# alexawrover.net
KiCad netlist of a schematic drawn in EAGLE
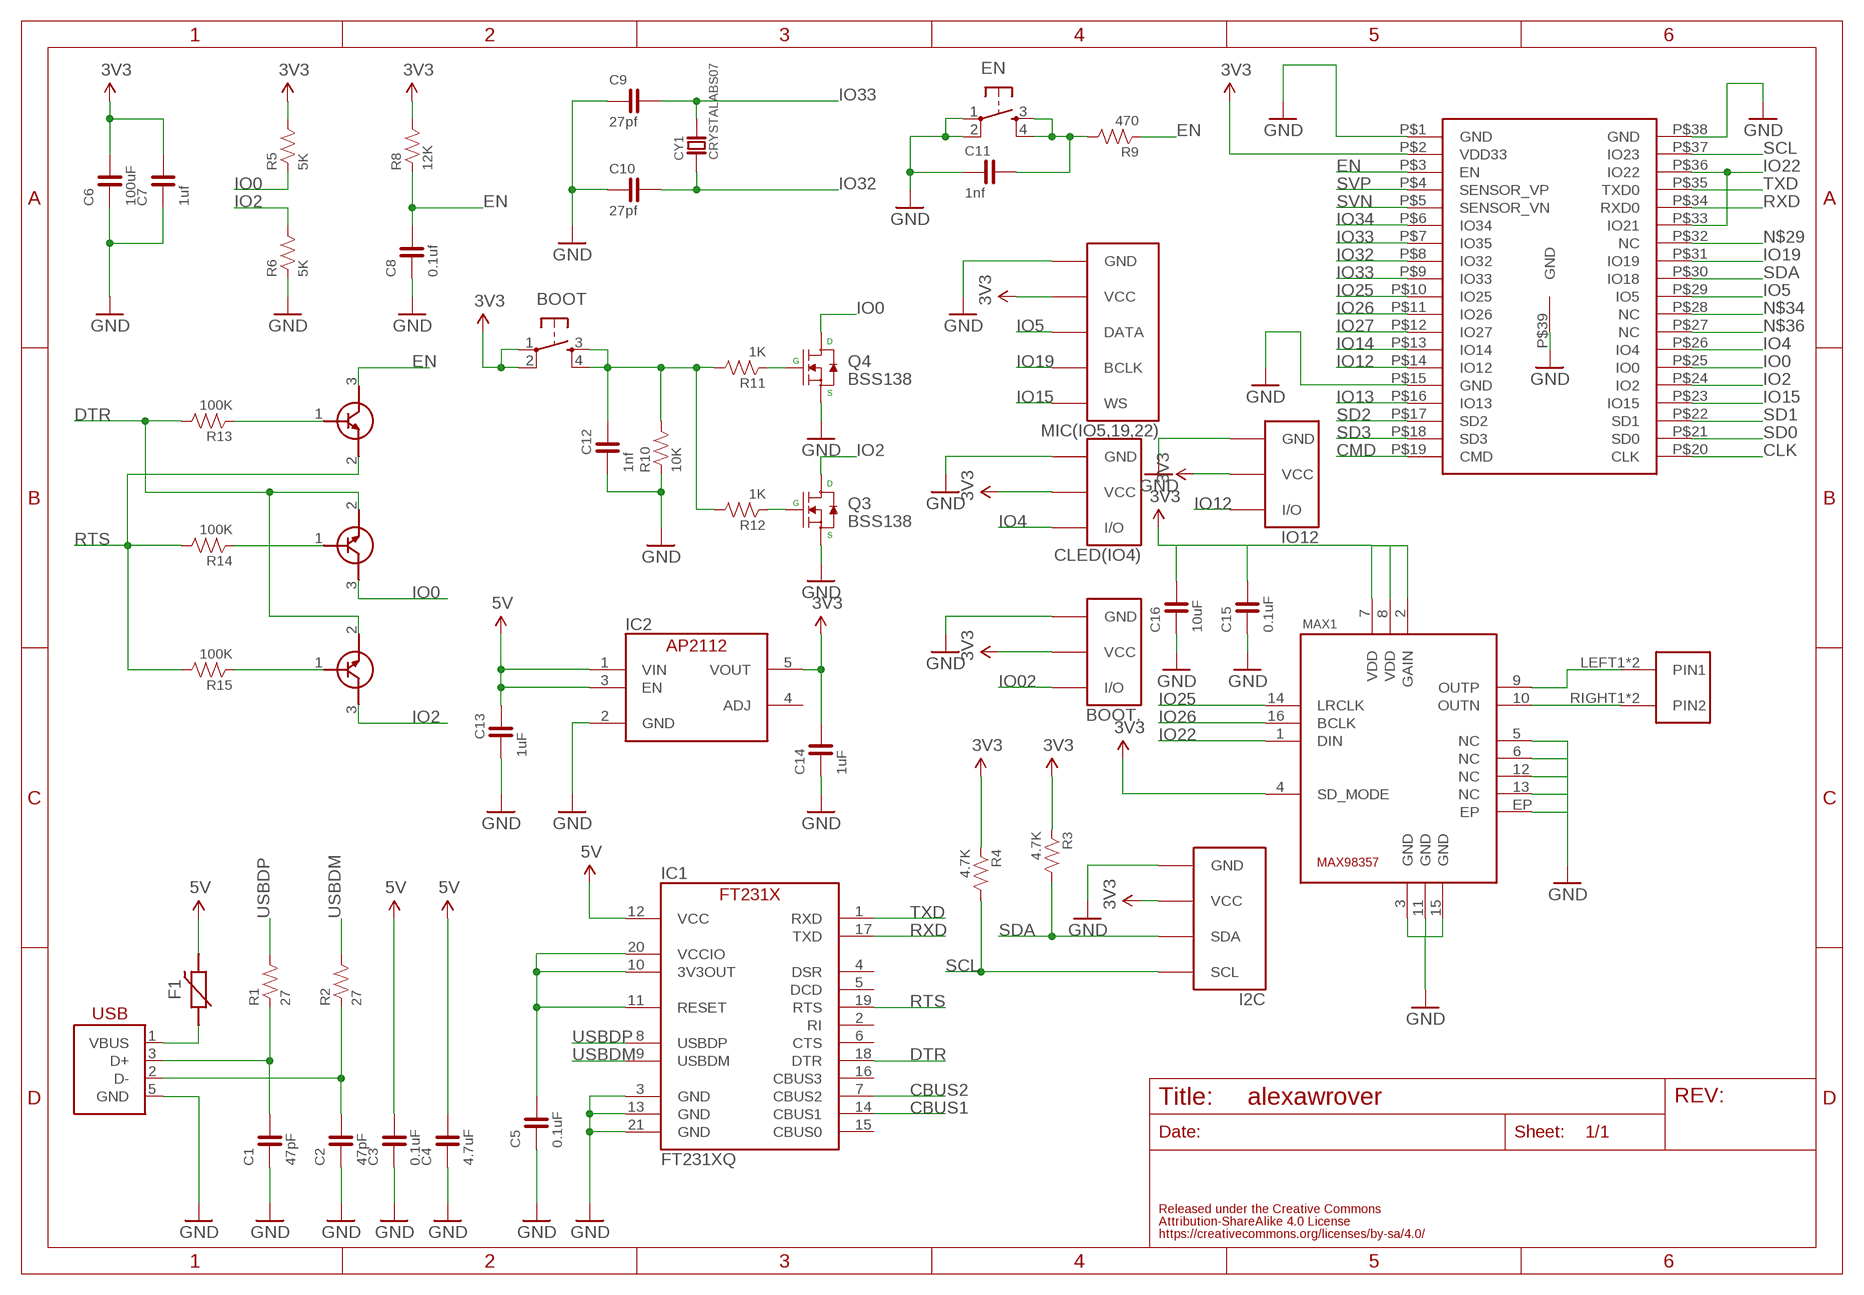
[diagram p0: schematic, sheet 1]

(export (version "E")
  (design (tool "Eeschema 10.0.6"))
  (components
    (comp (ref "BOOT")
      (value "TACT-SWITCH-SMD_KMR2")
      (footprint "eagle-import:KMR2")
      (libsource (lib "eagle-import") (part "TACT-SWITCH-SMD_KMR2"))
    )
    (comp (ref "BOOT.")
      (value "BUTTON")
      (footprint "eagle-import:FABO_BRICK_3PIN_B03B-PASK-1_NAME_BOTTOM")
      (libsource (lib "eagle-import") (part "FABO_BRICK_3PIN-03B-PASK-1_NAME_BOTTOM"))
    )
    (comp (ref "C1")
      (value "47pF")
      (footprint "eagle-import:0603-NARROW")
      (libsource (lib "eagle-import") (part "CAPACITOR-0603_NARROW"))
    )
    (comp (ref "C2")
      (value "47pF")
      (footprint "eagle-import:0603-NARROW")
      (libsource (lib "eagle-import") (part "CAPACITOR-0603_NARROW"))
    )
    (comp (ref "C3")
      (value "0.1uF")
      (footprint "eagle-import:0603-NARROW")
      (libsource (lib "eagle-import") (part "CAPACITOR-0603_NARROW"))
    )
    (comp (ref "C4")
      (value "4.7uF")
      (footprint "eagle-import:0603-NARROW")
      (libsource (lib "eagle-import") (part "CAPACITOR-0603_NARROW"))
    )
    (comp (ref "C5")
      (value "0.1uF")
      (footprint "eagle-import:0603-NARROW")
      (libsource (lib "eagle-import") (part "CAPACITOR-0603_NARROW"))
    )
    (comp (ref "C6")
      (value "100uF")
      (footprint "eagle-import:1206")
      (libsource (lib "eagle-import") (part "CAPACITOR-1206"))
    )
    (comp (ref "C7")
      (value "1uf")
      (footprint "eagle-import:0603-NARROW")
      (libsource (lib "eagle-import") (part "CAPACITOR-0603_NARROW"))
    )
    (comp (ref "C8")
      (value "0.1uf")
      (footprint "eagle-import:0603-NARROW")
      (libsource (lib "eagle-import") (part "CAPACITOR-0603_NARROW"))
    )
    (comp (ref "C9")
      (value "27pf")
      (footprint "eagle-import:0603-NARROW")
      (libsource (lib "eagle-import") (part "CAPACITOR-0603_NARROW"))
    )
    (comp (ref "C10")
      (value "27pf")
      (footprint "eagle-import:0603-NARROW")
      (libsource (lib "eagle-import") (part "CAPACITOR-0603_NARROW"))
    )
    (comp (ref "C11")
      (value "1nf")
      (footprint "eagle-import:0603-NARROW")
      (libsource (lib "eagle-import") (part "CAPACITOR-0603_NARROW"))
    )
    (comp (ref "C12")
      (value "1nf")
      (footprint "eagle-import:0603-NARROW")
      (libsource (lib "eagle-import") (part "CAPACITOR-0603_NARROW"))
    )
    (comp (ref "C13")
      (value "1uF")
      (footprint "eagle-import:0603")
      (libsource (lib "eagle-import") (part "CAPACITOR-0603"))
    )
    (comp (ref "C14")
      (value "1uF")
      (footprint "eagle-import:0603")
      (libsource (lib "eagle-import") (part "CAPACITOR-0603"))
    )
    (comp (ref "C15")
      (value "0.1uF")
      (footprint "eagle-import:0603")
      (libsource (lib "eagle-import") (part "CAPACITOR-0603"))
    )
    (comp (ref "C16")
      (value "10uF")
      (footprint "eagle-import:0603")
      (libsource (lib "eagle-import") (part "CAPACITOR-0603"))
    )
    (comp (ref "CLED(IO4)")
      (value "FABO_BRICK_3PIN-03B-PASK-1_NAME_BOTTOM")
      (footprint "eagle-import:FABO_BRICK_3PIN_B03B-PASK-1_NAME_BOTTOM")
      (libsource (lib "eagle-import") (part "FABO_BRICK_3PIN-03B-PASK-1_NAME_BOTTOM"))
    )
    (comp (ref "CY1")
      (value "CRYSTALABS07")
      (footprint "eagle-import:ABRACOM-ABS07-32.768KHZ")
      (libsource (lib "eagle-import") (part "CRYSTALABS07"))
    )
    (comp (ref "EN")
      (value "TACT-SWITCH-SMD_KMR2")
      (footprint "eagle-import:KMR2")
      (libsource (lib "eagle-import") (part "TACT-SWITCH-SMD_KMR2"))
    )
    (comp (ref "F1")
      (value "POLYSWITCH")
      (footprint "eagle-import:NANOSMDC035F")
      (libsource (lib "eagle-import") (part "POLYSWITCH"))
    )
    (comp (ref "I2C")
      (value "FABO_BRICK_I2C-B04B-PASK-1")
      (footprint "eagle-import:FABO_BRICK_I2C_B04B-PASK-1")
      (libsource (lib "eagle-import") (part "FABO_BRICK_I2C-B04B-PASK-1"))
    )
    (comp (ref "IC1")
      (value "FT231XQ")
      (footprint "eagle-import:QFN-20_FT231X")
      (libsource (lib "eagle-import") (part "FT231XQ"))
    )
    (comp (ref "IC2")
      (value "AP2112K-3.3TRG1")
      (footprint "eagle-import:SOT-23-5")
      (libsource (lib "eagle-import") (part "AP2112K-3.3TRG1"))
    )
    (comp (ref "IO12")
      (value "FABO_BRICK_3PIN-03B-PASK-1_NAME_BOTTOM")
      (footprint "eagle-import:FABO_BRICK_3PIN_B03B-PASK-1_NAME_BOTTOM")
      (libsource (lib "eagle-import") (part "FABO_BRICK_3PIN-03B-PASK-1_NAME_BOTTOM"))
    )
    (comp (ref "MAX1")
      (value "MA-MAX98357")
      (footprint "eagle-import:MAXIM-MAX98357")
      (libsource (lib "eagle-import") (part "MA-MAX98357"))
    )
    (comp (ref "MIC(IO5,19,22)")
      (value "FABO_BRICK_I2STOP")
      (footprint "eagle-import:FABO_BRICK_I2S_B05B-PARK-1")
      (libsource (lib "eagle-import") (part "FABO_BRICK_I2STOP"))
    )
    (comp (ref "Q3")
      (value "BSS138")
      (footprint "eagle-import:SOT23-3")
      (libsource (lib "eagle-import") (part "MOSFET-N-BSS138"))
    )
    (comp (ref "Q4")
      (value "BSS138")
      (footprint "eagle-import:SOT23-3")
      (libsource (lib "eagle-import") (part "MOSFET-N-BSS138"))
    )
    (comp (ref "R1")
      (value "27")
      (footprint "eagle-import:0603-NARROW")
      (libsource (lib "eagle-import") (part "RESISTOR-0603-NARROW"))
    )
    (comp (ref "R2")
      (value "27")
      (footprint "eagle-import:0603-NARROW")
      (libsource (lib "eagle-import") (part "RESISTOR-0603-NARROW"))
    )
    (comp (ref "R3")
      (value "4.7K")
      (footprint "eagle-import:0603-NARROW")
      (libsource (lib "eagle-import") (part "RESISTOR-0603-NARROW"))
    )
    (comp (ref "R4")
      (value "4.7K")
      (footprint "eagle-import:0603-NARROW")
      (libsource (lib "eagle-import") (part "RESISTOR-0603-NARROW"))
    )
    (comp (ref "R5")
      (value "5K")
      (footprint "eagle-import:0603-NARROW")
      (libsource (lib "eagle-import") (part "RESISTOR-0603-NARROW"))
    )
    (comp (ref "R6")
      (value "5K")
      (footprint "eagle-import:0603-NARROW")
      (libsource (lib "eagle-import") (part "RESISTOR-0603-NARROW"))
    )
    (comp (ref "R8")
      (value "12K")
      (footprint "eagle-import:0603-NARROW")
      (libsource (lib "eagle-import") (part "RESISTOR-0603-NARROW"))
    )
    (comp (ref "R9")
      (value "470")
      (footprint "eagle-import:0603-NARROW")
      (libsource (lib "eagle-import") (part "RESISTOR-0603-NARROW"))
    )
    (comp (ref "R10")
      (value "10K")
      (footprint "eagle-import:0603-NARROW")
      (libsource (lib "eagle-import") (part "RESISTOR-0603-NARROW"))
    )
    (comp (ref "R11")
      (value "1K")
      (footprint "eagle-import:0603-NARROW")
      (libsource (lib "eagle-import") (part "RESISTOR-0603-NARROW"))
    )
    (comp (ref "R12")
      (value "1K")
      (footprint "eagle-import:0603-NARROW")
      (libsource (lib "eagle-import") (part "RESISTOR-0603-NARROW"))
    )
    (comp (ref "R13")
      (value "100K")
      (footprint "eagle-import:0603-NARROW")
      (libsource (lib "eagle-import") (part "RESISTOR-0603-NARROW"))
    )
    (comp (ref "R14")
      (value "100K")
      (footprint "eagle-import:0603-NARROW")
      (libsource (lib "eagle-import") (part "RESISTOR-0603-NARROW"))
    )
    (comp (ref "R15")
      (value "100K")
      (footprint "eagle-import:0603-NARROW")
      (libsource (lib "eagle-import") (part "RESISTOR-0603-NARROW"))
    )
    (comp (ref "T1")
      (value "TRANSISTORMMBT2222")
      (footprint "eagle-import:SOT-23")
      (libsource (lib "eagle-import") (part "TRANSISTORMMBT2222"))
    )
    (comp (ref "T2")
      (value "TRANSISTORMMBT2222")
      (footprint "eagle-import:SOT-23")
      (libsource (lib "eagle-import") (part "TRANSISTORMMBT2222"))
    )
    (comp (ref "T3")
      (value "TRANSISTORMMBT2222")
      (footprint "eagle-import:SOT-23")
      (libsource (lib "eagle-import") (part "TRANSISTORMMBT2222"))
    )
    (comp (ref "U$1")
      (value "ESP32-WROVER")
      (footprint "eagle-import:ESP32-WROVER")
      (libsource (lib "eagle-import") (part "ESP32-WROVER"))
    )
    (comp (ref "U$4")
      (value "ML-1400-S1")
      (footprint "eagle-import:ML-1400-S1")
      (libsource (lib "eagle-import") (part "ML-1400-S1"))
    )
    (comp (ref "USB1")
      (value "USB-MICRO_B_SMT_HIROSE")
      (footprint "eagle-import:ZX62R-B-5P")
      (libsource (lib "eagle-import") (part "USB-MICRO_B_SMT_HIROSE"))
    )
  )
  (nets
    (net (code "1") (name "/CBUS1") (class "Default")
      (node (ref "IC1") (pin "14") (pinfunction "CBUS1_14") (pintype "bidirectional"))
    )
    (net (code "2") (name "/CBUS2") (class "Default")
      (node (ref "IC1") (pin "7") (pinfunction "CBUS2_7") (pintype "bidirectional"))
    )
    (net (code "3") (name "/CLK") (class "Default")
      (node (ref "U$1") (pin "P$20") (pinfunction "CLK_P$20") (pintype "bidirectional"))
    )
    (net (code "4") (name "/CMD") (class "Default")
      (node (ref "U$1") (pin "P$19") (pinfunction "CMD_P$19") (pintype "bidirectional"))
    )
    (net (code "5") (name "/DTR") (class "Default")
      (node (ref "IC1") (pin "18") (pinfunction "DTR_18") (pintype "bidirectional"))
      (node (ref "R13") (pin "2") (pinfunction "2_2") (pintype "bidirectional"))
      (node (ref "T2") (pin "2") (pinfunction "E_2") (pintype "bidirectional"))
      (node (ref "T3") (pin "2") (pinfunction "E_2") (pintype "bidirectional"))
    )
    (net (code "6") (name "/EN") (class "Default")
      (node (ref "C8") (pin "2") (pinfunction "2_2") (pintype "passive"))
      (node (ref "R8") (pin "1") (pinfunction "1_1") (pintype "bidirectional"))
      (node (ref "R9") (pin "1") (pinfunction "1_1") (pintype "bidirectional"))
      (node (ref "T1") (pin "3") (pinfunction "C_3") (pintype "bidirectional"))
      (node (ref "U$1") (pin "P$3") (pinfunction "EN_P$3") (pintype "bidirectional"))
    )
    (net (code "7") (name "/IO0") (class "Default")
      (node (ref "Q4") (pin "3") (pinfunction "D_3") (pintype "passive"))
      (node (ref "R5") (pin "1") (pinfunction "1_1") (pintype "bidirectional"))
      (node (ref "T2") (pin "3") (pinfunction "C_3") (pintype "bidirectional"))
      (node (ref "U$1") (pin "P$25") (pinfunction "IO0_P$25") (pintype "bidirectional"))
    )
    (net (code "8") (name "/IO2") (class "Default")
      (node (ref "Q3") (pin "3") (pinfunction "D_3") (pintype "passive"))
      (node (ref "R6") (pin "2") (pinfunction "2_2") (pintype "bidirectional"))
      (node (ref "T3") (pin "3") (pinfunction "C_3") (pintype "bidirectional"))
      (node (ref "U$1") (pin "P$24") (pinfunction "IO2_P$24") (pintype "bidirectional"))
    )
    (net (code "9") (name "/IO02") (class "Default")
      (node (ref "BOOT.") (pin "I/O") (pinfunction "I/O_I/O") (pintype "bidirectional"))
    )
    (net (code "10") (name "/IO4") (class "Default")
      (node (ref "CLED(IO4)") (pin "I/O") (pinfunction "I/O_I/O") (pintype "bidirectional"))
      (node (ref "U$1") (pin "P$26") (pinfunction "IO4_P$26") (pintype "bidirectional"))
    )
    (net (code "11") (name "/IO5") (class "Default")
      (node (ref "MIC(IO5,19,22)") (pin "DATA") (pinfunction "DATA_DATA") (pintype "bidirectional"))
      (node (ref "U$1") (pin "P$29") (pinfunction "IO5_P$29") (pintype "bidirectional"))
    )
    (net (code "12") (name "/IO12") (class "Default")
      (node (ref "IO12") (pin "I/O") (pinfunction "I/O_I/O") (pintype "bidirectional"))
      (node (ref "U$1") (pin "P$14") (pinfunction "IO12_P$14") (pintype "bidirectional"))
    )
    (net (code "13") (name "/IO13") (class "Default")
      (node (ref "U$1") (pin "P$16") (pinfunction "IO13_P$16") (pintype "bidirectional"))
    )
    (net (code "14") (name "/IO14") (class "Default")
      (node (ref "U$1") (pin "P$13") (pinfunction "IO14_P$13") (pintype "bidirectional"))
    )
    (net (code "15") (name "/IO15") (class "Default")
      (node (ref "MIC(IO5,19,22)") (pin "WS") (pinfunction "WS_WS") (pintype "bidirectional"))
      (node (ref "U$1") (pin "P$23") (pinfunction "IO15_P$23") (pintype "bidirectional"))
    )
    (net (code "16") (name "/IO19") (class "Default")
      (node (ref "MIC(IO5,19,22)") (pin "BCLK") (pinfunction "BCLK_BCLK") (pintype "bidirectional"))
      (node (ref "U$1") (pin "P$31") (pinfunction "IO19_P$31") (pintype "bidirectional"))
    )
    (net (code "17") (name "/IO22") (class "Default")
      (node (ref "MAX1") (pin "1") (pinfunction "DIN_1") (pintype "bidirectional"))
      (node (ref "U$1") (pin "P$33") (pinfunction "IO21_P$33") (pintype "bidirectional"))
      (node (ref "U$1") (pin "P$36") (pinfunction "IO22_P$36") (pintype "bidirectional"))
    )
    (net (code "18") (name "/IO25") (class "Default")
      (node (ref "MAX1") (pin "14") (pinfunction "LRCLK_14") (pintype "bidirectional"))
      (node (ref "U$1") (pin "P$10") (pinfunction "IO25_P$10") (pintype "bidirectional"))
    )
    (net (code "19") (name "/IO26") (class "Default")
      (node (ref "MAX1") (pin "16") (pinfunction "BCLK_16") (pintype "bidirectional"))
      (node (ref "U$1") (pin "P$11") (pinfunction "IO26_P$11") (pintype "bidirectional"))
    )
    (net (code "20") (name "/IO27") (class "Default")
      (node (ref "U$1") (pin "P$12") (pinfunction "IO27_P$12") (pintype "bidirectional"))
    )
    (net (code "21") (name "/IO32") (class "Default")
      (node (ref "C10") (pin "2") (pinfunction "2_2") (pintype "passive"))
      (node (ref "CY1") (pin "P$1") (pinfunction "P$1_P$1") (pintype "bidirectional"))
      (node (ref "U$1") (pin "P$8") (pinfunction "IO32_P$8") (pintype "bidirectional"))
    )
    (net (code "22") (name "/IO33") (class "Default")
      (node (ref "C9") (pin "2") (pinfunction "2_2") (pintype "passive"))
      (node (ref "CY1") (pin "P$2") (pinfunction "P$2_P$2") (pintype "bidirectional"))
      (node (ref "U$1") (pin "P$7") (pinfunction "IO35_P$7") (pintype "bidirectional"))
      (node (ref "U$1") (pin "P$9") (pinfunction "IO33_P$9") (pintype "bidirectional"))
    )
    (net (code "23") (name "/IO34") (class "Default")
      (node (ref "U$1") (pin "P$6") (pinfunction "IO34_P$6") (pintype "bidirectional"))
    )
    (net (code "24") (name "/N$29") (class "Default")
      (node (ref "U$1") (pin "P$32") (pinfunction "NC_P$32") (pintype "bidirectional"))
    )
    (net (code "25") (name "/N$34") (class "Default")
      (node (ref "U$1") (pin "P$28") (pinfunction "NC_P$28") (pintype "bidirectional"))
    )
    (net (code "26") (name "/N$36") (class "Default")
      (node (ref "U$1") (pin "P$27") (pinfunction "NC_P$27") (pintype "bidirectional"))
    )
    (net (code "27") (name "/RTS") (class "Default")
      (node (ref "IC1") (pin "19") (pinfunction "RTS_19") (pintype "bidirectional"))
      (node (ref "R14") (pin "2") (pinfunction "2_2") (pintype "bidirectional"))
      (node (ref "R15") (pin "2") (pinfunction "2_2") (pintype "bidirectional"))
      (node (ref "T1") (pin "2") (pinfunction "E_2") (pintype "bidirectional"))
    )
    (net (code "28") (name "/RXD") (class "Default")
      (node (ref "IC1") (pin "17") (pinfunction "TXD_17") (pintype "bidirectional"))
      (node (ref "U$1") (pin "P$34") (pinfunction "RXD0_P$34") (pintype "bidirectional"))
    )
    (net (code "29") (name "/SCL") (class "Default")
      (node (ref "I2C") (pin "SCL") (pinfunction "SCL_SCL") (pintype "bidirectional"))
      (node (ref "R4") (pin "2") (pinfunction "2_2") (pintype "bidirectional"))
      (node (ref "U$1") (pin "P$37") (pinfunction "IO23_P$37") (pintype "bidirectional"))
    )
    (net (code "30") (name "/SD0") (class "Default")
      (node (ref "U$1") (pin "P$21") (pinfunction "SD0_P$21") (pintype "bidirectional"))
    )
    (net (code "31") (name "/SD1") (class "Default")
      (node (ref "U$1") (pin "P$22") (pinfunction "SD1_P$22") (pintype "bidirectional"))
    )
    (net (code "32") (name "/SD2") (class "Default")
      (node (ref "U$1") (pin "P$17") (pinfunction "SD2_P$17") (pintype "bidirectional"))
    )
    (net (code "33") (name "/SD3") (class "Default")
      (node (ref "U$1") (pin "P$18") (pinfunction "SD3_P$18") (pintype "bidirectional"))
    )
    (net (code "34") (name "/SDA") (class "Default")
      (node (ref "I2C") (pin "SDA") (pinfunction "SDA_SDA") (pintype "bidirectional"))
      (node (ref "R3") (pin "2") (pinfunction "2_2") (pintype "bidirectional"))
      (node (ref "U$1") (pin "P$30") (pinfunction "IO18_P$30") (pintype "bidirectional"))
    )
    (net (code "35") (name "/SVN") (class "Default")
      (node (ref "U$1") (pin "P$5") (pinfunction "SENSOR_VN_P$5") (pintype "bidirectional"))
    )
    (net (code "36") (name "/SVP") (class "Default")
      (node (ref "U$1") (pin "P$4") (pinfunction "SENSOR_VP_P$4") (pintype "bidirectional"))
    )
    (net (code "37") (name "/TXD") (class "Default")
      (node (ref "IC1") (pin "1") (pinfunction "RXD_1") (pintype "bidirectional"))
      (node (ref "U$1") (pin "P$35") (pinfunction "TXD0_P$35") (pintype "bidirectional"))
    )
    (net (code "38") (name "/USBDM") (class "Default")
      (node (ref "IC1") (pin "9") (pinfunction "USBDM_9") (pintype "bidirectional"))
      (node (ref "R2") (pin "2") (pinfunction "2_2") (pintype "bidirectional"))
    )
    (net (code "39") (name "/USBDP") (class "Default")
      (node (ref "IC1") (pin "8") (pinfunction "USBDP_8") (pintype "bidirectional"))
      (node (ref "R1") (pin "2") (pinfunction "2_2") (pintype "bidirectional"))
    )
    (net (code "40") (name "3V3") (class "Default")
      (node (ref "BOOT") (pin "1") (pinfunction "1_1") (pintype "passive"))
      (node (ref "BOOT") (pin "2") (pinfunction "2_2") (pintype "passive"))
      (node (ref "BOOT.") (pin "VCC") (pinfunction "VCC_VCC") (pintype "bidirectional"))
      (node (ref "C14") (pin "2") (pinfunction "2_2") (pintype "passive"))
      (node (ref "C15") (pin "2") (pinfunction "2_2") (pintype "passive"))
      (node (ref "C16") (pin "2") (pinfunction "2_2") (pintype "passive"))
      (node (ref "C6") (pin "-") (pinfunction "2_-") (pintype "passive"))
      (node (ref "C7") (pin "2") (pinfunction "2_2") (pintype "passive"))
      (node (ref "CLED(IO4)") (pin "VCC") (pinfunction "VCC_VCC") (pintype "bidirectional"))
      (node (ref "I2C") (pin "VCC") (pinfunction "VCC_VCC") (pintype "bidirectional"))
      (node (ref "IC2") (pin "5") (pinfunction "VOUT_5") (pintype "bidirectional"))
      (node (ref "IO12") (pin "VCC") (pinfunction "VCC_VCC") (pintype "bidirectional"))
      (node (ref "MAX1") (pin "2") (pinfunction "GAIN_2") (pintype "bidirectional"))
      (node (ref "MAX1") (pin "4") (pinfunction "SD_MODE_4") (pintype "bidirectional"))
      (node (ref "MAX1") (pin "7") (pinfunction "VDD_7") (pintype "bidirectional"))
      (node (ref "MAX1") (pin "8") (pinfunction "VDD_8") (pintype "bidirectional"))
      (node (ref "MIC(IO5,19,22)") (pin "VCC") (pinfunction "VCC_VCC") (pintype "bidirectional"))
      (node (ref "R3") (pin "1") (pinfunction "1_1") (pintype "bidirectional"))
      (node (ref "R4") (pin "1") (pinfunction "1_1") (pintype "bidirectional"))
      (node (ref "R5") (pin "2") (pinfunction "2_2") (pintype "bidirectional"))
      (node (ref "R8") (pin "2") (pinfunction "2_2") (pintype "bidirectional"))
      (node (ref "U$1") (pin "P$2") (pinfunction "VDD33_P$2") (pintype "bidirectional"))
    )
    (net (code "41") (name "5V") (class "Default")
      (node (ref "C13") (pin "2") (pinfunction "2_2") (pintype "passive"))
      (node (ref "C3") (pin "2") (pinfunction "2_2") (pintype "passive"))
      (node (ref "C4") (pin "2") (pinfunction "2_2") (pintype "passive"))
      (node (ref "F1") (pin "2") (pinfunction "2_2") (pintype "bidirectional"))
      (node (ref "IC1") (pin "12") (pinfunction "VCC_12") (pintype "bidirectional"))
      (node (ref "IC2") (pin "1") (pinfunction "VIN_1") (pintype "bidirectional"))
      (node (ref "IC2") (pin "3") (pinfunction "EN_3") (pintype "bidirectional"))
    )
    (net (code "42") (name "GND") (class "Default")
      (node (ref "BOOT.") (pin "GND") (pinfunction "GND_GND") (pintype "bidirectional"))
      (node (ref "C1") (pin "1") (pinfunction "1_1") (pintype "passive"))
      (node (ref "C10") (pin "1") (pinfunction "1_1") (pintype "passive"))
      (node (ref "C11") (pin "1") (pinfunction "1_1") (pintype "passive"))
      (node (ref "C12") (pin "1") (pinfunction "1_1") (pintype "passive"))
      (node (ref "C13") (pin "1") (pinfunction "1_1") (pintype "passive"))
      (node (ref "C14") (pin "1") (pinfunction "1_1") (pintype "passive"))
      (node (ref "C15") (pin "1") (pinfunction "1_1") (pintype "passive"))
      (node (ref "C16") (pin "1") (pinfunction "1_1") (pintype "passive"))
      (node (ref "C2") (pin "1") (pinfunction "1_1") (pintype "passive"))
      (node (ref "C3") (pin "1") (pinfunction "1_1") (pintype "passive"))
      (node (ref "C4") (pin "1") (pinfunction "1_1") (pintype "passive"))
      (node (ref "C5") (pin "1") (pinfunction "1_1") (pintype "passive"))
      (node (ref "C6") (pin "+") (pinfunction "1_+") (pintype "passive"))
      (node (ref "C7") (pin "1") (pinfunction "1_1") (pintype "passive"))
      (node (ref "C8") (pin "1") (pinfunction "1_1") (pintype "passive"))
      (node (ref "C9") (pin "1") (pinfunction "1_1") (pintype "passive"))
      (node (ref "CLED(IO4)") (pin "GND") (pinfunction "GND_GND") (pintype "bidirectional"))
      (node (ref "EN") (pin "1") (pinfunction "1_1") (pintype "passive"))
      (node (ref "EN") (pin "2") (pinfunction "2_2") (pintype "passive"))
      (node (ref "I2C") (pin "GND") (pinfunction "GND_GND") (pintype "bidirectional"))
      (node (ref "IC1") (pin "13") (pinfunction "GND_13") (pintype "bidirectional"))
      (node (ref "IC1") (pin "21") (pinfunction "GND_21") (pintype "bidirectional"))
      (node (ref "IC1") (pin "3") (pinfunction "GND_3") (pintype "bidirectional"))
      (node (ref "IC2") (pin "2") (pinfunction "GND_2") (pintype "bidirectional"))
      (node (ref "IO12") (pin "GND") (pinfunction "GND_GND") (pintype "bidirectional"))
      (node (ref "MAX1") (pin "11") (pinfunction "GND_11") (pintype "bidirectional"))
      (node (ref "MAX1") (pin "12") (pinfunction "NC_12") (pintype "bidirectional"))
      (node (ref "MAX1") (pin "13") (pinfunction "NC_13") (pintype "bidirectional"))
      (node (ref "MAX1") (pin "15") (pinfunction "GND_15") (pintype "bidirectional"))
      (node (ref "MAX1") (pin "3") (pinfunction "GND_3") (pintype "bidirectional"))
      (node (ref "MAX1") (pin "5") (pinfunction "NC_5") (pintype "bidirectional"))
      (node (ref "MAX1") (pin "6") (pinfunction "NC_6") (pintype "bidirectional"))
      (node (ref "MAX1") (pin "EP") (pinfunction "EP_EP") (pintype "bidirectional"))
      (node (ref "MIC(IO5,19,22)") (pin "GND") (pinfunction "GND_GND") (pintype "bidirectional"))
      (node (ref "Q3") (pin "2") (pinfunction "S_2") (pintype "passive"))
      (node (ref "Q4") (pin "2") (pinfunction "S_2") (pintype "passive"))
      (node (ref "R10") (pin "1") (pinfunction "1_1") (pintype "bidirectional"))
      (node (ref "R6") (pin "1") (pinfunction "1_1") (pintype "bidirectional"))
      (node (ref "U$1") (pin "P$1") (pinfunction "GND_P$1") (pintype "bidirectional"))
      (node (ref "U$1") (pin "P$15") (pinfunction "GND_P$15") (pintype "bidirectional"))
      (node (ref "U$1") (pin "P$38") (pinfunction "GND_P$38") (pintype "bidirectional"))
      (node (ref "U$1") (pin "P$39") (pinfunction "GND_P$39") (pintype "bidirectional"))
      (node (ref "USB1") (pin "5") (pinfunction "GND_5") (pintype "bidirectional"))
    )
    (net (code "43") (name "Net-(BOOT-Pad3)") (class "Default")
      (node (ref "BOOT") (pin "3") (pinfunction "3_3") (pintype "passive"))
      (node (ref "BOOT") (pin "4") (pinfunction "4_4") (pintype "passive"))
      (node (ref "C12") (pin "2") (pinfunction "2_2") (pintype "passive"))
      (node (ref "R10") (pin "2") (pinfunction "2_2") (pintype "bidirectional"))
      (node (ref "R11") (pin "2") (pinfunction "2_2") (pintype "bidirectional"))
      (node (ref "R12") (pin "2") (pinfunction "2_2") (pintype "bidirectional"))
    )
    (net (code "44") (name "Net-(C11-Pad2)") (class "Default")
      (node (ref "C11") (pin "2") (pinfunction "2_2") (pintype "passive"))
      (node (ref "EN") (pin "3") (pinfunction "3_3") (pintype "passive"))
      (node (ref "EN") (pin "4") (pinfunction "4_4") (pintype "passive"))
      (node (ref "R9") (pin "2") (pinfunction "2_2") (pintype "bidirectional"))
    )
    (net (code "45") (name "Net-(IC1-3V3OUT)") (class "Default")
      (node (ref "C5") (pin "2") (pinfunction "2_2") (pintype "passive"))
      (node (ref "IC1") (pin "10") (pinfunction "3V3OUT_10") (pintype "bidirectional"))
      (node (ref "IC1") (pin "11") (pinfunction "RESET_11") (pintype "bidirectional"))
      (node (ref "IC1") (pin "20") (pinfunction "VCCIO_20") (pintype "bidirectional"))
    )
    (net (code "46") (name "Net-(MAX1-OUTN)") (class "Default")
      (node (ref "MAX1") (pin "10") (pinfunction "OUTN_10") (pintype "bidirectional"))
      (node (ref "U$4") (pin "RIGHT1") (pinfunction "PIN2_RIGHT1") (pintype "bidirectional"))
      (node (ref "U$4") (pin "RIGHT2") (pinfunction "PIN2_RIGHT2") (pintype "bidirectional"))
    )
    (net (code "47") (name "Net-(MAX1-OUTP)") (class "Default")
      (node (ref "MAX1") (pin "9") (pinfunction "OUTP_9") (pintype "bidirectional"))
      (node (ref "U$4") (pin "LEFT1") (pinfunction "PIN1_LEFT1") (pintype "bidirectional"))
      (node (ref "U$4") (pin "LEFT2") (pinfunction "PIN1_LEFT2") (pintype "bidirectional"))
    )
    (net (code "48") (name "Net-(Q3-G)") (class "Default")
      (node (ref "Q3") (pin "1") (pinfunction "G_1") (pintype "passive"))
      (node (ref "R12") (pin "1") (pinfunction "1_1") (pintype "bidirectional"))
    )
    (net (code "49") (name "Net-(Q4-G)") (class "Default")
      (node (ref "Q4") (pin "1") (pinfunction "G_1") (pintype "passive"))
      (node (ref "R11") (pin "1") (pinfunction "1_1") (pintype "bidirectional"))
    )
    (net (code "50") (name "Net-(T1-B)") (class "Default")
      (node (ref "R13") (pin "1") (pinfunction "1_1") (pintype "bidirectional"))
      (node (ref "T1") (pin "1") (pinfunction "B_1") (pintype "bidirectional"))
    )
    (net (code "51") (name "Net-(T2-B)") (class "Default")
      (node (ref "R14") (pin "1") (pinfunction "1_1") (pintype "bidirectional"))
      (node (ref "T2") (pin "1") (pinfunction "B_1") (pintype "bidirectional"))
    )
    (net (code "52") (name "Net-(T3-B)") (class "Default")
      (node (ref "R15") (pin "1") (pinfunction "1_1") (pintype "bidirectional"))
      (node (ref "T3") (pin "1") (pinfunction "B_1") (pintype "bidirectional"))
    )
    (net (code "53") (name "Net-(USB1-D+)") (class "Default")
      (node (ref "C1") (pin "2") (pinfunction "2_2") (pintype "passive"))
      (node (ref "R1") (pin "1") (pinfunction "1_1") (pintype "bidirectional"))
      (node (ref "USB1") (pin "3") (pinfunction "D+_3") (pintype "bidirectional"))
    )
    (net (code "54") (name "Net-(USB1-D-)") (class "Default")
      (node (ref "C2") (pin "2") (pinfunction "2_2") (pintype "passive"))
      (node (ref "R2") (pin "1") (pinfunction "1_1") (pintype "bidirectional"))
      (node (ref "USB1") (pin "2") (pinfunction "D-_2") (pintype "bidirectional"))
    )
    (net (code "55") (name "Net-(USB1-VBUS)") (class "Default")
      (node (ref "F1") (pin "1") (pinfunction "1_1") (pintype "bidirectional"))
      (node (ref "USB1") (pin "1") (pinfunction "VBUS_1") (pintype "bidirectional"))
    )
    (net (code "56") (name "unconnected-(IC1-CBUS0-Pad15)") (class "Default")
      (node (ref "IC1") (pin "15") (pinfunction "CBUS0_15") (pintype "bidirectional"))
    )
    (net (code "57") (name "unconnected-(IC1-CBUS3-Pad16)") (class "Default")
      (node (ref "IC1") (pin "16") (pinfunction "CBUS3_16") (pintype "bidirectional"))
    )
    (net (code "58") (name "unconnected-(IC1-CTS-Pad6)") (class "Default")
      (node (ref "IC1") (pin "6") (pinfunction "CTS_6") (pintype "bidirectional"))
    )
    (net (code "59") (name "unconnected-(IC1-DCD-Pad5)") (class "Default")
      (node (ref "IC1") (pin "5") (pinfunction "DCD_5") (pintype "bidirectional"))
    )
    (net (code "60") (name "unconnected-(IC1-DSR-Pad4)") (class "Default")
      (node (ref "IC1") (pin "4") (pinfunction "DSR_4") (pintype "bidirectional"))
    )
    (net (code "61") (name "unconnected-(IC1-RI-Pad2)") (class "Default")
      (node (ref "IC1") (pin "2") (pinfunction "RI_2") (pintype "bidirectional"))
    )
    (net (code "62") (name "unconnected-(IC2-ADJ-Pad4)") (class "Default")
      (node (ref "IC2") (pin "4") (pinfunction "ADJ_4") (pintype "bidirectional"))
    )
  )
)
